# Drivers.net
KiCad netlist of a schematic drawn in Altium Designer
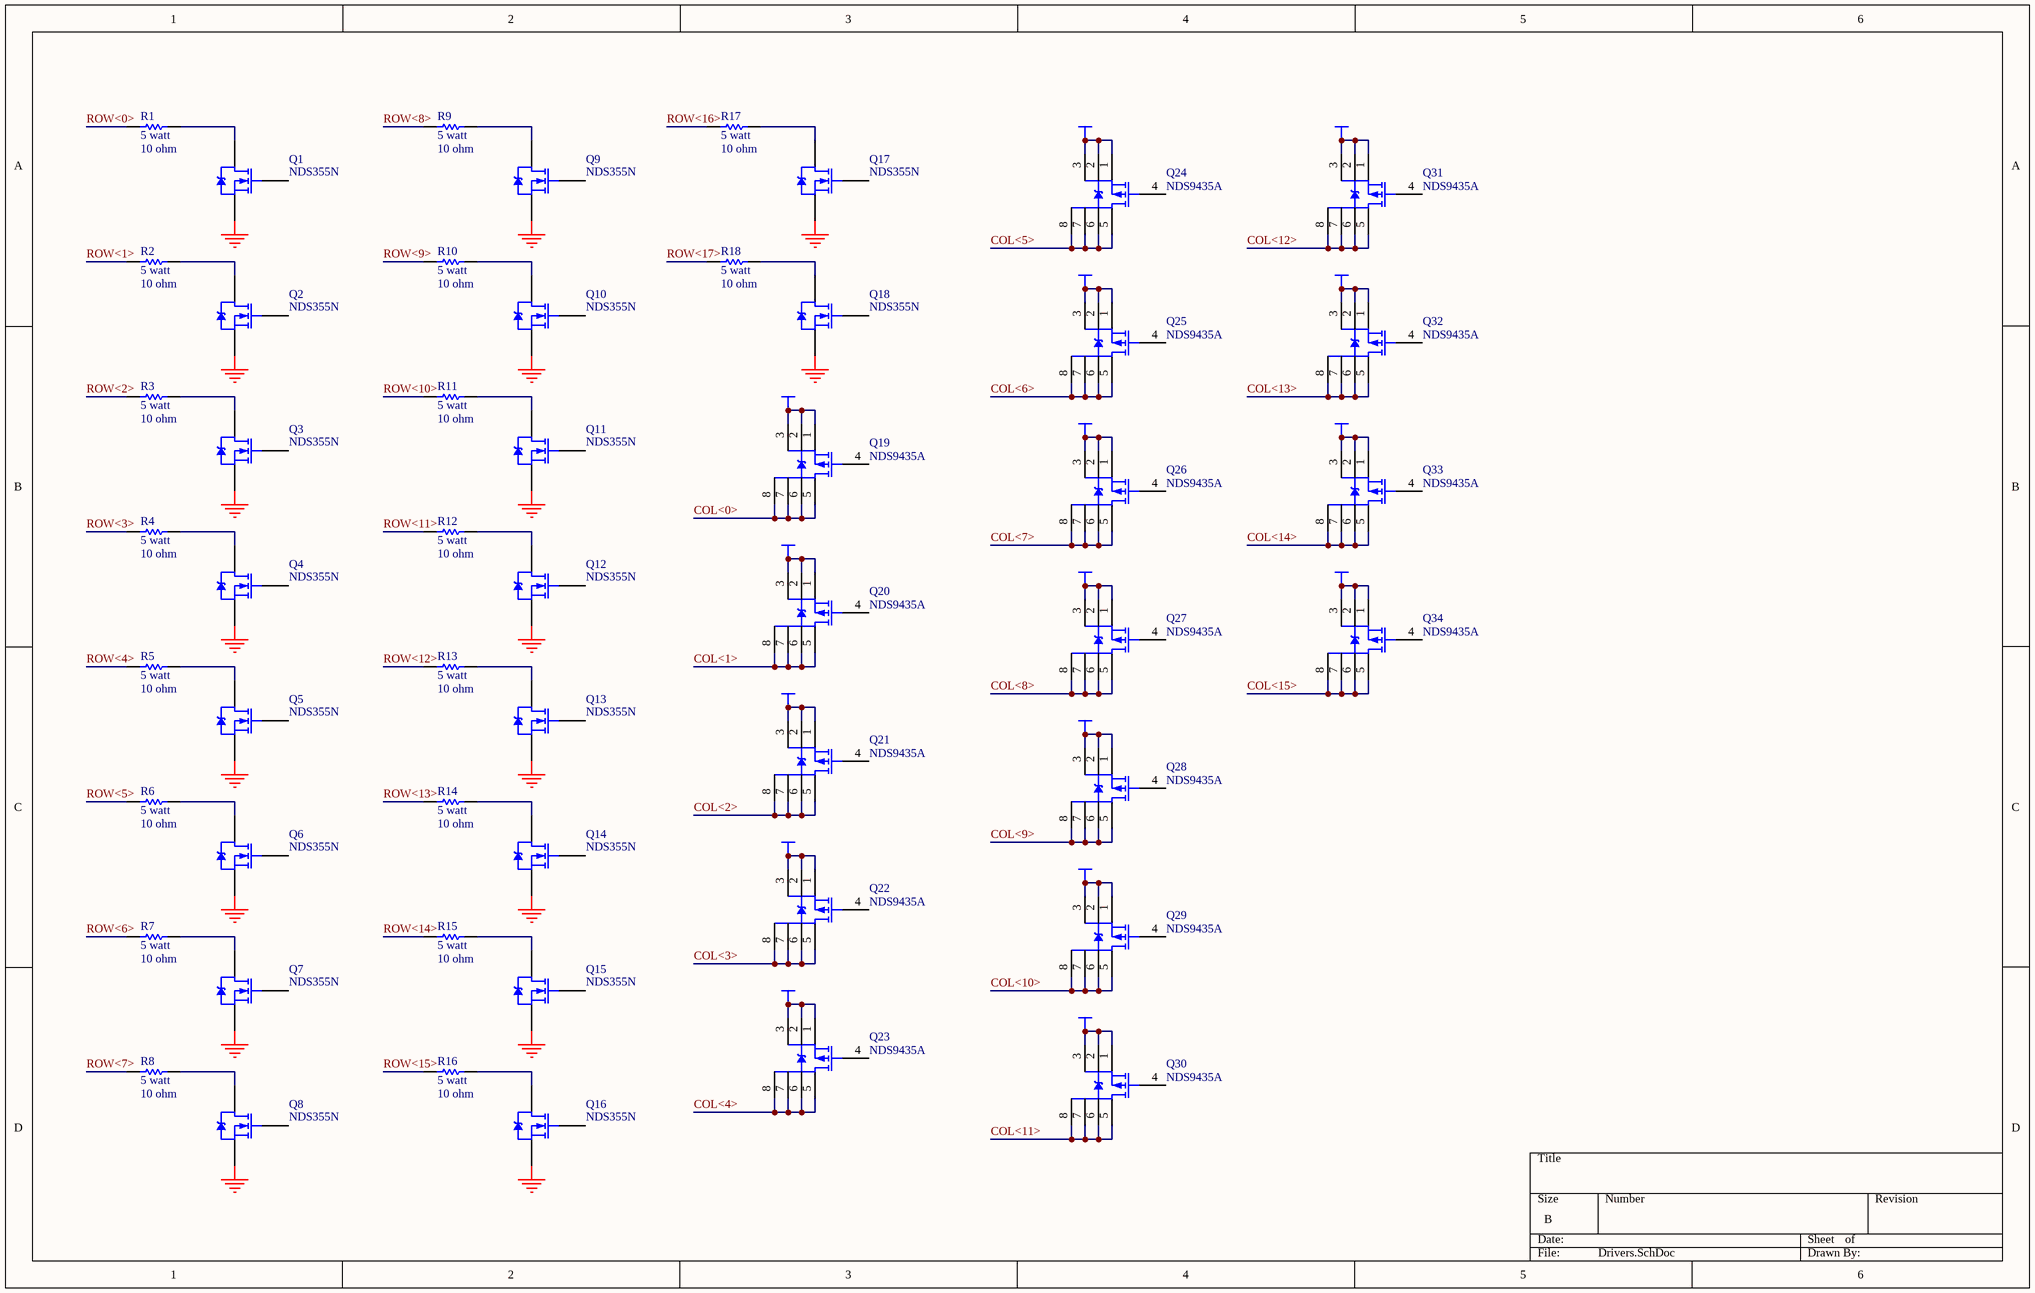
[diagram p0: Drivers.SchDoc]

(export (version "E")
  (design (tool "Eeschema 10.0.6"))
  (components
    (comp (ref "Q1")
      (value "NDS355N")
      (footprint "SO-G3")
      (description "N-Channel Logic Level Enhancement Mode FET")
      (fields (field (name "MANUFACTURER") "Fairchild"))
      (libsource (lib "Schlib1") (part "NDS355N"))
    )
    (comp (ref "Q2")
      (value "NDS355N")
      (footprint "SO-G3")
      (description "N-Channel Logic Level Enhancement Mode FET")
      (fields (field (name "MANUFACTURER") "Fairchild"))
      (libsource (lib "Schlib1") (part "NDS355N"))
    )
    (comp (ref "Q3")
      (value "NDS355N")
      (footprint "SO-G3")
      (description "N-Channel Logic Level Enhancement Mode FET")
      (fields (field (name "MANUFACTURER") "Fairchild"))
      (libsource (lib "Schlib1") (part "NDS355N"))
    )
    (comp (ref "Q4")
      (value "NDS355N")
      (footprint "SO-G3")
      (description "N-Channel Logic Level Enhancement Mode FET")
      (fields (field (name "MANUFACTURER") "Fairchild"))
      (libsource (lib "Schlib1") (part "NDS355N"))
    )
    (comp (ref "Q5")
      (value "NDS355N")
      (footprint "SO-G3")
      (description "N-Channel Logic Level Enhancement Mode FET")
      (fields (field (name "MANUFACTURER") "Fairchild"))
      (libsource (lib "Schlib1") (part "NDS355N"))
    )
    (comp (ref "Q6")
      (value "NDS355N")
      (footprint "SO-G3")
      (description "N-Channel Logic Level Enhancement Mode FET")
      (fields (field (name "MANUFACTURER") "Fairchild"))
      (libsource (lib "Schlib1") (part "NDS355N"))
    )
    (comp (ref "Q7")
      (value "NDS355N")
      (footprint "SO-G3")
      (description "N-Channel Logic Level Enhancement Mode FET")
      (fields (field (name "MANUFACTURER") "Fairchild"))
      (libsource (lib "Schlib1") (part "NDS355N"))
    )
    (comp (ref "Q8")
      (value "NDS355N")
      (footprint "SO-G3")
      (description "N-Channel Logic Level Enhancement Mode FET")
      (fields (field (name "MANUFACTURER") "Fairchild"))
      (libsource (lib "Schlib1") (part "NDS355N"))
    )
    (comp (ref "Q9")
      (value "NDS355N")
      (footprint "SO-G3")
      (description "N-Channel Logic Level Enhancement Mode FET")
      (fields (field (name "MANUFACTURER") "Fairchild"))
      (libsource (lib "Schlib1") (part "NDS355N"))
    )
    (comp (ref "Q10")
      (value "NDS355N")
      (footprint "SO-G3")
      (description "N-Channel Logic Level Enhancement Mode FET")
      (fields (field (name "MANUFACTURER") "Fairchild"))
      (libsource (lib "Schlib1") (part "NDS355N"))
    )
    (comp (ref "Q11")
      (value "NDS355N")
      (footprint "SO-G3")
      (description "N-Channel Logic Level Enhancement Mode FET")
      (fields (field (name "MANUFACTURER") "Fairchild"))
      (libsource (lib "Schlib1") (part "NDS355N"))
    )
    (comp (ref "Q12")
      (value "NDS355N")
      (footprint "SO-G3")
      (description "N-Channel Logic Level Enhancement Mode FET")
      (fields (field (name "MANUFACTURER") "Fairchild"))
      (libsource (lib "Schlib1") (part "NDS355N"))
    )
    (comp (ref "Q13")
      (value "NDS355N")
      (footprint "SO-G3")
      (description "N-Channel Logic Level Enhancement Mode FET")
      (fields (field (name "MANUFACTURER") "Fairchild"))
      (libsource (lib "Schlib1") (part "NDS355N"))
    )
    (comp (ref "Q14")
      (value "NDS355N")
      (footprint "SO-G3")
      (description "N-Channel Logic Level Enhancement Mode FET")
      (fields (field (name "MANUFACTURER") "Fairchild"))
      (libsource (lib "Schlib1") (part "NDS355N"))
    )
    (comp (ref "Q15")
      (value "NDS355N")
      (footprint "SO-G3")
      (description "N-Channel Logic Level Enhancement Mode FET")
      (fields (field (name "MANUFACTURER") "Fairchild"))
      (libsource (lib "Schlib1") (part "NDS355N"))
    )
    (comp (ref "Q16")
      (value "NDS355N")
      (footprint "SO-G3")
      (description "N-Channel Logic Level Enhancement Mode FET")
      (fields (field (name "MANUFACTURER") "Fairchild"))
      (libsource (lib "Schlib1") (part "NDS355N"))
    )
    (comp (ref "Q17")
      (value "NDS355N")
      (footprint "SO-G3")
      (description "N-Channel Logic Level Enhancement Mode FET")
      (fields (field (name "MANUFACTURER") "Fairchild"))
      (libsource (lib "Schlib1") (part "NDS355N"))
    )
    (comp (ref "Q18")
      (value "NDS355N")
      (footprint "SO-G3")
      (description "N-Channel Logic Level Enhancement Mode FET")
      (fields (field (name "MANUFACTURER") "Fairchild"))
      (libsource (lib "Schlib1") (part "NDS355N"))
    )
    (comp (ref "Q19")
      (value "NDS9435A")
      (footprint "SO-G8")
      (description "30V P-Channel PowerTrench MOSFET")
      (fields (field (name "MANUFACTURER") "Fairchild"))
      (libsource (lib "Schlib1") (part "NDS9435A"))
    )
    (comp (ref "Q20")
      (value "NDS9435A")
      (footprint "SO-G8")
      (description "30V P-Channel PowerTrench MOSFET")
      (fields (field (name "MANUFACTURER") "Fairchild"))
      (libsource (lib "Schlib1") (part "NDS9435A"))
    )
    (comp (ref "Q21")
      (value "NDS9435A")
      (footprint "SO-G8")
      (description "30V P-Channel PowerTrench MOSFET")
      (fields (field (name "MANUFACTURER") "Fairchild"))
      (libsource (lib "Schlib1") (part "NDS9435A"))
    )
    (comp (ref "Q22")
      (value "NDS9435A")
      (footprint "SO-G8")
      (description "30V P-Channel PowerTrench MOSFET")
      (fields (field (name "MANUFACTURER") "Fairchild"))
      (libsource (lib "Schlib1") (part "NDS9435A"))
    )
    (comp (ref "Q23")
      (value "NDS9435A")
      (footprint "SO-G8")
      (description "30V P-Channel PowerTrench MOSFET")
      (fields (field (name "MANUFACTURER") "Fairchild"))
      (libsource (lib "Schlib1") (part "NDS9435A"))
    )
    (comp (ref "Q24")
      (value "NDS9435A")
      (footprint "SO-G8")
      (description "30V P-Channel PowerTrench MOSFET")
      (fields (field (name "MANUFACTURER") "Fairchild"))
      (libsource (lib "Schlib1") (part "NDS9435A"))
    )
    (comp (ref "Q25")
      (value "NDS9435A")
      (footprint "SO-G8")
      (description "30V P-Channel PowerTrench MOSFET")
      (fields (field (name "MANUFACTURER") "Fairchild"))
      (libsource (lib "Schlib1") (part "NDS9435A"))
    )
    (comp (ref "Q26")
      (value "NDS9435A")
      (footprint "SO-G8")
      (description "30V P-Channel PowerTrench MOSFET")
      (fields (field (name "MANUFACTURER") "Fairchild"))
      (libsource (lib "Schlib1") (part "NDS9435A"))
    )
    (comp (ref "Q27")
      (value "NDS9435A")
      (footprint "SO-G8")
      (description "30V P-Channel PowerTrench MOSFET")
      (fields (field (name "MANUFACTURER") "Fairchild"))
      (libsource (lib "Schlib1") (part "NDS9435A"))
    )
    (comp (ref "Q28")
      (value "NDS9435A")
      (footprint "SO-G8")
      (description "30V P-Channel PowerTrench MOSFET")
      (fields (field (name "MANUFACTURER") "Fairchild"))
      (libsource (lib "Schlib1") (part "NDS9435A"))
    )
    (comp (ref "Q29")
      (value "NDS9435A")
      (footprint "SO-G8")
      (description "30V P-Channel PowerTrench MOSFET")
      (fields (field (name "MANUFACTURER") "Fairchild"))
      (libsource (lib "Schlib1") (part "NDS9435A"))
    )
    (comp (ref "Q30")
      (value "NDS9435A")
      (footprint "SO-G8")
      (description "30V P-Channel PowerTrench MOSFET")
      (fields (field (name "MANUFACTURER") "Fairchild"))
      (libsource (lib "Schlib1") (part "NDS9435A"))
    )
    (comp (ref "Q31")
      (value "NDS9435A")
      (footprint "SO-G8")
      (description "30V P-Channel PowerTrench MOSFET")
      (fields (field (name "MANUFACTURER") "Fairchild"))
      (libsource (lib "Schlib1") (part "NDS9435A"))
    )
    (comp (ref "Q32")
      (value "NDS9435A")
      (footprint "SO-G8")
      (description "30V P-Channel PowerTrench MOSFET")
      (fields (field (name "MANUFACTURER") "Fairchild"))
      (libsource (lib "Schlib1") (part "NDS9435A"))
    )
    (comp (ref "Q33")
      (value "NDS9435A")
      (footprint "SO-G8")
      (description "30V P-Channel PowerTrench MOSFET")
      (fields (field (name "MANUFACTURER") "Fairchild"))
      (libsource (lib "Schlib1") (part "NDS9435A"))
    )
    (comp (ref "Q34")
      (value "NDS9435A")
      (footprint "SO-G8")
      (description "30V P-Channel PowerTrench MOSFET")
      (fields (field (name "MANUFACTURER") "Fairchild"))
      (libsource (lib "Schlib1") (part "NDS9435A"))
    )
    (comp (ref "R1")
      (value "5 watt")
      (footprint "AXIAL-1.0")
      (description "Resistor")
      (fields
        (field (name "MANUFACTURER") "Generic Components")
        (field (name "ALTIUM_VALUE") "10 ohm")
        (field (name "PUBLISHER") "Altium Limited")
      )
      (libsource (lib "Miscellaneous Devices") (part "Res1"))
    )
    (comp (ref "R2")
      (value "5 watt")
      (footprint "AXIAL-1.0")
      (description "Resistor")
      (fields
        (field (name "MANUFACTURER") "Generic Components")
        (field (name "ALTIUM_VALUE") "10 ohm")
        (field (name "PUBLISHER") "Altium Limited")
      )
      (libsource (lib "Miscellaneous Devices") (part "Res1"))
    )
    (comp (ref "R3")
      (value "5 watt")
      (footprint "AXIAL-1.0")
      (description "Resistor")
      (fields
        (field (name "MANUFACTURER") "Generic Components")
        (field (name "ALTIUM_VALUE") "10 ohm")
        (field (name "PUBLISHER") "Altium Limited")
      )
      (libsource (lib "Miscellaneous Devices") (part "Res1"))
    )
    (comp (ref "R4")
      (value "5 watt")
      (footprint "AXIAL-1.0")
      (description "Resistor")
      (fields
        (field (name "MANUFACTURER") "Generic Components")
        (field (name "ALTIUM_VALUE") "10 ohm")
        (field (name "PUBLISHER") "Altium Limited")
      )
      (libsource (lib "Miscellaneous Devices") (part "Res1"))
    )
    (comp (ref "R5")
      (value "5 watt")
      (footprint "AXIAL-1.0")
      (description "Resistor")
      (fields
        (field (name "MANUFACTURER") "Generic Components")
        (field (name "ALTIUM_VALUE") "10 ohm")
        (field (name "PUBLISHER") "Altium Limited")
      )
      (libsource (lib "Miscellaneous Devices") (part "Res1"))
    )
    (comp (ref "R6")
      (value "5 watt")
      (footprint "AXIAL-1.0")
      (description "Resistor")
      (fields
        (field (name "MANUFACTURER") "Generic Components")
        (field (name "ALTIUM_VALUE") "10 ohm")
        (field (name "PUBLISHER") "Altium Limited")
      )
      (libsource (lib "Miscellaneous Devices") (part "Res1"))
    )
    (comp (ref "R7")
      (value "5 watt")
      (footprint "AXIAL-1.0")
      (description "Resistor")
      (fields
        (field (name "MANUFACTURER") "Generic Components")
        (field (name "ALTIUM_VALUE") "10 ohm")
        (field (name "PUBLISHER") "Altium Limited")
      )
      (libsource (lib "Miscellaneous Devices") (part "Res1"))
    )
    (comp (ref "R8")
      (value "5 watt")
      (footprint "AXIAL-1.0")
      (description "Resistor")
      (fields
        (field (name "MANUFACTURER") "Generic Components")
        (field (name "ALTIUM_VALUE") "10 ohm")
        (field (name "PUBLISHER") "Altium Limited")
      )
      (libsource (lib "Miscellaneous Devices") (part "Res1"))
    )
    (comp (ref "R9")
      (value "5 watt")
      (footprint "AXIAL-1.0")
      (description "Resistor")
      (fields
        (field (name "MANUFACTURER") "Generic Components")
        (field (name "ALTIUM_VALUE") "10 ohm")
        (field (name "PUBLISHER") "Altium Limited")
      )
      (libsource (lib "Miscellaneous Devices") (part "Res1"))
    )
    (comp (ref "R10")
      (value "5 watt")
      (footprint "AXIAL-1.0")
      (description "Resistor")
      (fields
        (field (name "MANUFACTURER") "Generic Components")
        (field (name "ALTIUM_VALUE") "10 ohm")
        (field (name "PUBLISHER") "Altium Limited")
      )
      (libsource (lib "Miscellaneous Devices") (part "Res1"))
    )
    (comp (ref "R11")
      (value "5 watt")
      (footprint "AXIAL-1.0")
      (description "Resistor")
      (fields
        (field (name "MANUFACTURER") "Generic Components")
        (field (name "ALTIUM_VALUE") "10 ohm")
        (field (name "PUBLISHER") "Altium Limited")
      )
      (libsource (lib "Miscellaneous Devices") (part "Res1"))
    )
    (comp (ref "R12")
      (value "5 watt")
      (footprint "AXIAL-1.0")
      (description "Resistor")
      (fields
        (field (name "MANUFACTURER") "Generic Components")
        (field (name "ALTIUM_VALUE") "10 ohm")
        (field (name "PUBLISHER") "Altium Limited")
      )
      (libsource (lib "Miscellaneous Devices") (part "Res1"))
    )
    (comp (ref "R13")
      (value "5 watt")
      (footprint "AXIAL-1.0")
      (description "Resistor")
      (fields
        (field (name "MANUFACTURER") "Generic Components")
        (field (name "ALTIUM_VALUE") "10 ohm")
        (field (name "PUBLISHER") "Altium Limited")
      )
      (libsource (lib "Miscellaneous Devices") (part "Res1"))
    )
    (comp (ref "R14")
      (value "5 watt")
      (footprint "AXIAL-1.0")
      (description "Resistor")
      (fields
        (field (name "MANUFACTURER") "Generic Components")
        (field (name "ALTIUM_VALUE") "10 ohm")
        (field (name "PUBLISHER") "Altium Limited")
      )
      (libsource (lib "Miscellaneous Devices") (part "Res1"))
    )
    (comp (ref "R15")
      (value "5 watt")
      (footprint "AXIAL-1.0")
      (description "Resistor")
      (fields
        (field (name "MANUFACTURER") "Generic Components")
        (field (name "ALTIUM_VALUE") "10 ohm")
        (field (name "PUBLISHER") "Altium Limited")
      )
      (libsource (lib "Miscellaneous Devices") (part "Res1"))
    )
    (comp (ref "R16")
      (value "5 watt")
      (footprint "AXIAL-1.0")
      (description "Resistor")
      (fields
        (field (name "MANUFACTURER") "Generic Components")
        (field (name "ALTIUM_VALUE") "10 ohm")
        (field (name "PUBLISHER") "Altium Limited")
      )
      (libsource (lib "Miscellaneous Devices") (part "Res1"))
    )
    (comp (ref "R17")
      (value "5 watt")
      (footprint "AXIAL-1.0")
      (description "Resistor")
      (fields
        (field (name "MANUFACTURER") "Generic Components")
        (field (name "ALTIUM_VALUE") "10 ohm")
        (field (name "PUBLISHER") "Altium Limited")
      )
      (libsource (lib "Miscellaneous Devices") (part "Res1"))
    )
    (comp (ref "R18")
      (value "5 watt")
      (footprint "AXIAL-1.0")
      (description "Resistor")
      (fields
        (field (name "MANUFACTURER") "Generic Components")
        (field (name "ALTIUM_VALUE") "10 ohm")
        (field (name "PUBLISHER") "Altium Limited")
      )
      (libsource (lib "Miscellaneous Devices") (part "Res1"))
    )
  )
  (nets
    (net (code "1") (name "+5") (class "Default")
      (node (ref "Q19") (pin "1") (pinfunction "S_1") (pintype "passive"))
      (node (ref "Q19") (pin "2") (pinfunction "S_2") (pintype "passive"))
      (node (ref "Q19") (pin "3") (pinfunction "S_3") (pintype "passive"))
      (node (ref "Q20") (pin "1") (pinfunction "S_1") (pintype "passive"))
      (node (ref "Q20") (pin "2") (pinfunction "S_2") (pintype "passive"))
      (node (ref "Q20") (pin "3") (pinfunction "S_3") (pintype "passive"))
      (node (ref "Q21") (pin "1") (pinfunction "S_1") (pintype "passive"))
      (node (ref "Q21") (pin "2") (pinfunction "S_2") (pintype "passive"))
      (node (ref "Q21") (pin "3") (pinfunction "S_3") (pintype "passive"))
      (node (ref "Q22") (pin "1") (pinfunction "S_1") (pintype "passive"))
      (node (ref "Q22") (pin "2") (pinfunction "S_2") (pintype "passive"))
      (node (ref "Q22") (pin "3") (pinfunction "S_3") (pintype "passive"))
      (node (ref "Q23") (pin "1") (pinfunction "S_1") (pintype "passive"))
      (node (ref "Q23") (pin "2") (pinfunction "S_2") (pintype "passive"))
      (node (ref "Q23") (pin "3") (pinfunction "S_3") (pintype "passive"))
      (node (ref "Q24") (pin "1") (pinfunction "S_1") (pintype "passive"))
      (node (ref "Q24") (pin "2") (pinfunction "S_2") (pintype "passive"))
      (node (ref "Q24") (pin "3") (pinfunction "S_3") (pintype "passive"))
      (node (ref "Q25") (pin "1") (pinfunction "S_1") (pintype "passive"))
      (node (ref "Q25") (pin "2") (pinfunction "S_2") (pintype "passive"))
      (node (ref "Q25") (pin "3") (pinfunction "S_3") (pintype "passive"))
      (node (ref "Q26") (pin "1") (pinfunction "S_1") (pintype "passive"))
      (node (ref "Q26") (pin "2") (pinfunction "S_2") (pintype "passive"))
      (node (ref "Q26") (pin "3") (pinfunction "S_3") (pintype "passive"))
      (node (ref "Q27") (pin "1") (pinfunction "S_1") (pintype "passive"))
      (node (ref "Q27") (pin "2") (pinfunction "S_2") (pintype "passive"))
      (node (ref "Q27") (pin "3") (pinfunction "S_3") (pintype "passive"))
      (node (ref "Q28") (pin "1") (pinfunction "S_1") (pintype "passive"))
      (node (ref "Q28") (pin "2") (pinfunction "S_2") (pintype "passive"))
      (node (ref "Q28") (pin "3") (pinfunction "S_3") (pintype "passive"))
      (node (ref "Q29") (pin "1") (pinfunction "S_1") (pintype "passive"))
      (node (ref "Q29") (pin "2") (pinfunction "S_2") (pintype "passive"))
      (node (ref "Q29") (pin "3") (pinfunction "S_3") (pintype "passive"))
      (node (ref "Q30") (pin "1") (pinfunction "S_1") (pintype "passive"))
      (node (ref "Q30") (pin "2") (pinfunction "S_2") (pintype "passive"))
      (node (ref "Q30") (pin "3") (pinfunction "S_3") (pintype "passive"))
      (node (ref "Q31") (pin "1") (pinfunction "S_1") (pintype "passive"))
      (node (ref "Q31") (pin "2") (pinfunction "S_2") (pintype "passive"))
      (node (ref "Q31") (pin "3") (pinfunction "S_3") (pintype "passive"))
      (node (ref "Q32") (pin "1") (pinfunction "S_1") (pintype "passive"))
      (node (ref "Q32") (pin "2") (pinfunction "S_2") (pintype "passive"))
      (node (ref "Q32") (pin "3") (pinfunction "S_3") (pintype "passive"))
      (node (ref "Q33") (pin "1") (pinfunction "S_1") (pintype "passive"))
      (node (ref "Q33") (pin "2") (pinfunction "S_2") (pintype "passive"))
      (node (ref "Q33") (pin "3") (pinfunction "S_3") (pintype "passive"))
      (node (ref "Q34") (pin "1") (pinfunction "S_1") (pintype "passive"))
      (node (ref "Q34") (pin "2") (pinfunction "S_2") (pintype "passive"))
      (node (ref "Q34") (pin "3") (pinfunction "S_3") (pintype "passive"))
    )
    (net (code "2") (name "/COL<0>") (class "Default")
      (node (ref "Q19") (pin "5") (pinfunction "D_5") (pintype "passive"))
      (node (ref "Q19") (pin "6") (pinfunction "D_6") (pintype "passive"))
      (node (ref "Q19") (pin "7") (pinfunction "D_7") (pintype "passive"))
      (node (ref "Q19") (pin "8") (pinfunction "D_8") (pintype "passive"))
    )
    (net (code "3") (name "/COL<1>") (class "Default")
      (node (ref "Q20") (pin "5") (pinfunction "D_5") (pintype "passive"))
      (node (ref "Q20") (pin "6") (pinfunction "D_6") (pintype "passive"))
      (node (ref "Q20") (pin "7") (pinfunction "D_7") (pintype "passive"))
      (node (ref "Q20") (pin "8") (pinfunction "D_8") (pintype "passive"))
    )
    (net (code "4") (name "/COL<2>") (class "Default")
      (node (ref "Q21") (pin "5") (pinfunction "D_5") (pintype "passive"))
      (node (ref "Q21") (pin "6") (pinfunction "D_6") (pintype "passive"))
      (node (ref "Q21") (pin "7") (pinfunction "D_7") (pintype "passive"))
      (node (ref "Q21") (pin "8") (pinfunction "D_8") (pintype "passive"))
    )
    (net (code "5") (name "/COL<3>") (class "Default")
      (node (ref "Q22") (pin "5") (pinfunction "D_5") (pintype "passive"))
      (node (ref "Q22") (pin "6") (pinfunction "D_6") (pintype "passive"))
      (node (ref "Q22") (pin "7") (pinfunction "D_7") (pintype "passive"))
      (node (ref "Q22") (pin "8") (pinfunction "D_8") (pintype "passive"))
    )
    (net (code "6") (name "/COL<4>") (class "Default")
      (node (ref "Q23") (pin "5") (pinfunction "D_5") (pintype "passive"))
      (node (ref "Q23") (pin "6") (pinfunction "D_6") (pintype "passive"))
      (node (ref "Q23") (pin "7") (pinfunction "D_7") (pintype "passive"))
      (node (ref "Q23") (pin "8") (pinfunction "D_8") (pintype "passive"))
    )
    (net (code "7") (name "/COL<5>") (class "Default")
      (node (ref "Q24") (pin "5") (pinfunction "D_5") (pintype "passive"))
      (node (ref "Q24") (pin "6") (pinfunction "D_6") (pintype "passive"))
      (node (ref "Q24") (pin "7") (pinfunction "D_7") (pintype "passive"))
      (node (ref "Q24") (pin "8") (pinfunction "D_8") (pintype "passive"))
    )
    (net (code "8") (name "/COL<6>") (class "Default")
      (node (ref "Q25") (pin "5") (pinfunction "D_5") (pintype "passive"))
      (node (ref "Q25") (pin "6") (pinfunction "D_6") (pintype "passive"))
      (node (ref "Q25") (pin "7") (pinfunction "D_7") (pintype "passive"))
      (node (ref "Q25") (pin "8") (pinfunction "D_8") (pintype "passive"))
    )
    (net (code "9") (name "/COL<7>") (class "Default")
      (node (ref "Q26") (pin "5") (pinfunction "D_5") (pintype "passive"))
      (node (ref "Q26") (pin "6") (pinfunction "D_6") (pintype "passive"))
      (node (ref "Q26") (pin "7") (pinfunction "D_7") (pintype "passive"))
      (node (ref "Q26") (pin "8") (pinfunction "D_8") (pintype "passive"))
    )
    (net (code "10") (name "/COL<8>") (class "Default")
      (node (ref "Q27") (pin "5") (pinfunction "D_5") (pintype "passive"))
      (node (ref "Q27") (pin "6") (pinfunction "D_6") (pintype "passive"))
      (node (ref "Q27") (pin "7") (pinfunction "D_7") (pintype "passive"))
      (node (ref "Q27") (pin "8") (pinfunction "D_8") (pintype "passive"))
    )
    (net (code "11") (name "/COL<9>") (class "Default")
      (node (ref "Q28") (pin "5") (pinfunction "D_5") (pintype "passive"))
      (node (ref "Q28") (pin "6") (pinfunction "D_6") (pintype "passive"))
      (node (ref "Q28") (pin "7") (pinfunction "D_7") (pintype "passive"))
      (node (ref "Q28") (pin "8") (pinfunction "D_8") (pintype "passive"))
    )
    (net (code "12") (name "/COL<10>") (class "Default")
      (node (ref "Q29") (pin "5") (pinfunction "D_5") (pintype "passive"))
      (node (ref "Q29") (pin "6") (pinfunction "D_6") (pintype "passive"))
      (node (ref "Q29") (pin "7") (pinfunction "D_7") (pintype "passive"))
      (node (ref "Q29") (pin "8") (pinfunction "D_8") (pintype "passive"))
    )
    (net (code "13") (name "/COL<11>") (class "Default")
      (node (ref "Q30") (pin "5") (pinfunction "D_5") (pintype "passive"))
      (node (ref "Q30") (pin "6") (pinfunction "D_6") (pintype "passive"))
      (node (ref "Q30") (pin "7") (pinfunction "D_7") (pintype "passive"))
      (node (ref "Q30") (pin "8") (pinfunction "D_8") (pintype "passive"))
    )
    (net (code "14") (name "/COL<12>") (class "Default")
      (node (ref "Q31") (pin "5") (pinfunction "D_5") (pintype "passive"))
      (node (ref "Q31") (pin "6") (pinfunction "D_6") (pintype "passive"))
      (node (ref "Q31") (pin "7") (pinfunction "D_7") (pintype "passive"))
      (node (ref "Q31") (pin "8") (pinfunction "D_8") (pintype "passive"))
    )
    (net (code "15") (name "/COL<13>") (class "Default")
      (node (ref "Q32") (pin "5") (pinfunction "D_5") (pintype "passive"))
      (node (ref "Q32") (pin "6") (pinfunction "D_6") (pintype "passive"))
      (node (ref "Q32") (pin "7") (pinfunction "D_7") (pintype "passive"))
      (node (ref "Q32") (pin "8") (pinfunction "D_8") (pintype "passive"))
    )
    (net (code "16") (name "/COL<14>") (class "Default")
      (node (ref "Q33") (pin "5") (pinfunction "D_5") (pintype "passive"))
      (node (ref "Q33") (pin "6") (pinfunction "D_6") (pintype "passive"))
      (node (ref "Q33") (pin "7") (pinfunction "D_7") (pintype "passive"))
      (node (ref "Q33") (pin "8") (pinfunction "D_8") (pintype "passive"))
    )
    (net (code "17") (name "/COL<15>") (class "Default")
      (node (ref "Q34") (pin "5") (pinfunction "D_5") (pintype "passive"))
      (node (ref "Q34") (pin "6") (pinfunction "D_6") (pintype "passive"))
      (node (ref "Q34") (pin "7") (pinfunction "D_7") (pintype "passive"))
      (node (ref "Q34") (pin "8") (pinfunction "D_8") (pintype "passive"))
    )
    (net (code "18") (name "/ROW<0>") (class "Default")
      (node (ref "R1") (pin "1") (pinfunction "1_1") (pintype "passive"))
    )
    (net (code "19") (name "/ROW<1>") (class "Default")
      (node (ref "R2") (pin "1") (pinfunction "1_1") (pintype "passive"))
    )
    (net (code "20") (name "/ROW<2>") (class "Default")
      (node (ref "R3") (pin "1") (pinfunction "1_1") (pintype "passive"))
    )
    (net (code "21") (name "/ROW<3>") (class "Default")
      (node (ref "R4") (pin "1") (pinfunction "1_1") (pintype "passive"))
    )
    (net (code "22") (name "/ROW<4>") (class "Default")
      (node (ref "R5") (pin "1") (pinfunction "1_1") (pintype "passive"))
    )
    (net (code "23") (name "/ROW<5>") (class "Default")
      (node (ref "R6") (pin "1") (pinfunction "1_1") (pintype "passive"))
    )
    (net (code "24") (name "/ROW<6>") (class "Default")
      (node (ref "R7") (pin "1") (pinfunction "1_1") (pintype "passive"))
    )
    (net (code "25") (name "/ROW<7>") (class "Default")
      (node (ref "R8") (pin "1") (pinfunction "1_1") (pintype "passive"))
    )
    (net (code "26") (name "/ROW<8>") (class "Default")
      (node (ref "R9") (pin "1") (pinfunction "1_1") (pintype "passive"))
    )
    (net (code "27") (name "/ROW<9>") (class "Default")
      (node (ref "R10") (pin "1") (pinfunction "1_1") (pintype "passive"))
    )
    (net (code "28") (name "/ROW<10>") (class "Default")
      (node (ref "R11") (pin "1") (pinfunction "1_1") (pintype "passive"))
    )
    (net (code "29") (name "/ROW<11>") (class "Default")
      (node (ref "R12") (pin "1") (pinfunction "1_1") (pintype "passive"))
    )
    (net (code "30") (name "/ROW<12>") (class "Default")
      (node (ref "R13") (pin "1") (pinfunction "1_1") (pintype "passive"))
    )
    (net (code "31") (name "/ROW<13>") (class "Default")
      (node (ref "R14") (pin "1") (pinfunction "1_1") (pintype "passive"))
    )
    (net (code "32") (name "/ROW<14>") (class "Default")
      (node (ref "R15") (pin "1") (pinfunction "1_1") (pintype "passive"))
    )
    (net (code "33") (name "/ROW<15>") (class "Default")
      (node (ref "R16") (pin "1") (pinfunction "1_1") (pintype "passive"))
    )
    (net (code "34") (name "/ROW<16>") (class "Default")
      (node (ref "R17") (pin "1") (pinfunction "1_1") (pintype "passive"))
    )
    (net (code "35") (name "/ROW<17>") (class "Default")
      (node (ref "R18") (pin "1") (pinfunction "1_1") (pintype "passive"))
    )
    (net (code "36") (name "GND") (class "Default")
      (node (ref "Q1") (pin "2") (pinfunction "S_2") (pintype "passive"))
      (node (ref "Q10") (pin "2") (pinfunction "S_2") (pintype "passive"))
      (node (ref "Q11") (pin "2") (pinfunction "S_2") (pintype "passive"))
      (node (ref "Q12") (pin "2") (pinfunction "S_2") (pintype "passive"))
      (node (ref "Q13") (pin "2") (pinfunction "S_2") (pintype "passive"))
      (node (ref "Q14") (pin "2") (pinfunction "S_2") (pintype "passive"))
      (node (ref "Q15") (pin "2") (pinfunction "S_2") (pintype "passive"))
      (node (ref "Q16") (pin "2") (pinfunction "S_2") (pintype "passive"))
      (node (ref "Q17") (pin "2") (pinfunction "S_2") (pintype "passive"))
      (node (ref "Q18") (pin "2") (pinfunction "S_2") (pintype "passive"))
      (node (ref "Q2") (pin "2") (pinfunction "S_2") (pintype "passive"))
      (node (ref "Q3") (pin "2") (pinfunction "S_2") (pintype "passive"))
      (node (ref "Q4") (pin "2") (pinfunction "S_2") (pintype "passive"))
      (node (ref "Q5") (pin "2") (pinfunction "S_2") (pintype "passive"))
      (node (ref "Q6") (pin "2") (pinfunction "S_2") (pintype "passive"))
      (node (ref "Q7") (pin "2") (pinfunction "S_2") (pintype "passive"))
      (node (ref "Q8") (pin "2") (pinfunction "S_2") (pintype "passive"))
      (node (ref "Q9") (pin "2") (pinfunction "S_2") (pintype "passive"))
    )
    (net (code "37") (name "Net-(Q1-D)") (class "Default")
      (node (ref "Q1") (pin "3") (pinfunction "D_3") (pintype "passive"))
      (node (ref "R1") (pin "2") (pinfunction "2_2") (pintype "passive"))
    )
    (net (code "38") (name "Net-(Q2-D)") (class "Default")
      (node (ref "Q2") (pin "3") (pinfunction "D_3") (pintype "passive"))
      (node (ref "R2") (pin "2") (pinfunction "2_2") (pintype "passive"))
    )
    (net (code "39") (name "Net-(Q3-D)") (class "Default")
      (node (ref "Q3") (pin "3") (pinfunction "D_3") (pintype "passive"))
      (node (ref "R3") (pin "2") (pinfunction "2_2") (pintype "passive"))
    )
    (net (code "40") (name "Net-(Q4-D)") (class "Default")
      (node (ref "Q4") (pin "3") (pinfunction "D_3") (pintype "passive"))
      (node (ref "R4") (pin "2") (pinfunction "2_2") (pintype "passive"))
    )
    (net (code "41") (name "Net-(Q5-D)") (class "Default")
      (node (ref "Q5") (pin "3") (pinfunction "D_3") (pintype "passive"))
      (node (ref "R5") (pin "2") (pinfunction "2_2") (pintype "passive"))
    )
    (net (code "42") (name "Net-(Q6-D)") (class "Default")
      (node (ref "Q6") (pin "3") (pinfunction "D_3") (pintype "passive"))
      (node (ref "R6") (pin "2") (pinfunction "2_2") (pintype "passive"))
    )
    (net (code "43") (name "Net-(Q7-D)") (class "Default")
      (node (ref "Q7") (pin "3") (pinfunction "D_3") (pintype "passive"))
      (node (ref "R7") (pin "2") (pinfunction "2_2") (pintype "passive"))
    )
    (net (code "44") (name "Net-(Q8-D)") (class "Default")
      (node (ref "Q8") (pin "3") (pinfunction "D_3") (pintype "passive"))
      (node (ref "R8") (pin "2") (pinfunction "2_2") (pintype "passive"))
    )
    (net (code "45") (name "Net-(Q9-D)") (class "Default")
      (node (ref "Q9") (pin "3") (pinfunction "D_3") (pintype "passive"))
      (node (ref "R9") (pin "2") (pinfunction "2_2") (pintype "passive"))
    )
    (net (code "46") (name "Net-(Q10-D)") (class "Default")
      (node (ref "Q10") (pin "3") (pinfunction "D_3") (pintype "passive"))
      (node (ref "R10") (pin "2") (pinfunction "2_2") (pintype "passive"))
    )
    (net (code "47") (name "Net-(Q11-D)") (class "Default")
      (node (ref "Q11") (pin "3") (pinfunction "D_3") (pintype "passive"))
      (node (ref "R11") (pin "2") (pinfunction "2_2") (pintype "passive"))
    )
    (net (code "48") (name "Net-(Q12-D)") (class "Default")
      (node (ref "Q12") (pin "3") (pinfunction "D_3") (pintype "passive"))
      (node (ref "R12") (pin "2") (pinfunction "2_2") (pintype "passive"))
    )
    (net (code "49") (name "Net-(Q13-D)") (class "Default")
      (node (ref "Q13") (pin "3") (pinfunction "D_3") (pintype "passive"))
      (node (ref "R13") (pin "2") (pinfunction "2_2") (pintype "passive"))
    )
    (net (code "50") (name "Net-(Q14-D)") (class "Default")
      (node (ref "Q14") (pin "3") (pinfunction "D_3") (pintype "passive"))
      (node (ref "R14") (pin "2") (pinfunction "2_2") (pintype "passive"))
    )
    (net (code "51") (name "Net-(Q15-D)") (class "Default")
      (node (ref "Q15") (pin "3") (pinfunction "D_3") (pintype "passive"))
      (node (ref "R15") (pin "2") (pinfunction "2_2") (pintype "passive"))
    )
    (net (code "52") (name "Net-(Q16-D)") (class "Default")
      (node (ref "Q16") (pin "3") (pinfunction "D_3") (pintype "passive"))
      (node (ref "R16") (pin "2") (pinfunction "2_2") (pintype "passive"))
    )
    (net (code "53") (name "Net-(Q17-D)") (class "Default")
      (node (ref "Q17") (pin "3") (pinfunction "D_3") (pintype "passive"))
      (node (ref "R17") (pin "2") (pinfunction "2_2") (pintype "passive"))
    )
    (net (code "54") (name "Net-(Q18-D)") (class "Default")
      (node (ref "Q18") (pin "3") (pinfunction "D_3") (pintype "passive"))
      (node (ref "R18") (pin "2") (pinfunction "2_2") (pintype "passive"))
    )
    (net (code "55") (name "unconnected-(Q1-G-Pad1)") (class "Default")
      (node (ref "Q1") (pin "1") (pinfunction "G_1") (pintype "passive"))
    )
    (net (code "56") (name "unconnected-(Q2-G-Pad1)") (class "Default")
      (node (ref "Q2") (pin "1") (pinfunction "G_1") (pintype "passive"))
    )
    (net (code "57") (name "unconnected-(Q3-G-Pad1)") (class "Default")
      (node (ref "Q3") (pin "1") (pinfunction "G_1") (pintype "passive"))
    )
    (net (code "58") (name "unconnected-(Q4-G-Pad1)") (class "Default")
      (node (ref "Q4") (pin "1") (pinfunction "G_1") (pintype "passive"))
    )
    (net (code "59") (name "unconnected-(Q5-G-Pad1)") (class "Default")
      (node (ref "Q5") (pin "1") (pinfunction "G_1") (pintype "passive"))
    )
    (net (code "60") (name "unconnected-(Q6-G-Pad1)") (class "Default")
      (node (ref "Q6") (pin "1") (pinfunction "G_1") (pintype "passive"))
    )
    (net (code "61") (name "unconnected-(Q7-G-Pad1)") (class "Default")
      (node (ref "Q7") (pin "1") (pinfunction "G_1") (pintype "passive"))
    )
    (net (code "62") (name "unconnected-(Q8-G-Pad1)") (class "Default")
      (node (ref "Q8") (pin "1") (pinfunction "G_1") (pintype "passive"))
    )
    (net (code "63") (name "unconnected-(Q9-G-Pad1)") (class "Default")
      (node (ref "Q9") (pin "1") (pinfunction "G_1") (pintype "passive"))
    )
    (net (code "64") (name "unconnected-(Q10-G-Pad1)") (class "Default")
      (node (ref "Q10") (pin "1") (pinfunction "G_1") (pintype "passive"))
    )
    (net (code "65") (name "unconnected-(Q11-G-Pad1)") (class "Default")
      (node (ref "Q11") (pin "1") (pinfunction "G_1") (pintype "passive"))
    )
    (net (code "66") (name "unconnected-(Q12-G-Pad1)") (class "Default")
      (node (ref "Q12") (pin "1") (pinfunction "G_1") (pintype "passive"))
    )
    (net (code "67") (name "unconnected-(Q13-G-Pad1)") (class "Default")
      (node (ref "Q13") (pin "1") (pinfunction "G_1") (pintype "passive"))
    )
    (net (code "68") (name "unconnected-(Q14-G-Pad1)") (class "Default")
      (node (ref "Q14") (pin "1") (pinfunction "G_1") (pintype "passive"))
    )
    (net (code "69") (name "unconnected-(Q15-G-Pad1)") (class "Default")
      (node (ref "Q15") (pin "1") (pinfunction "G_1") (pintype "passive"))
    )
    (net (code "70") (name "unconnected-(Q16-G-Pad1)") (class "Default")
      (node (ref "Q16") (pin "1") (pinfunction "G_1") (pintype "passive"))
    )
    (net (code "71") (name "unconnected-(Q17-G-Pad1)") (class "Default")
      (node (ref "Q17") (pin "1") (pinfunction "G_1") (pintype "passive"))
    )
    (net (code "72") (name "unconnected-(Q18-G-Pad1)") (class "Default")
      (node (ref "Q18") (pin "1") (pinfunction "G_1") (pintype "passive"))
    )
    (net (code "73") (name "unconnected-(Q19-G-Pad4)") (class "Default")
      (node (ref "Q19") (pin "4") (pinfunction "G_4") (pintype "passive"))
    )
    (net (code "74") (name "unconnected-(Q20-G-Pad4)") (class "Default")
      (node (ref "Q20") (pin "4") (pinfunction "G_4") (pintype "passive"))
    )
    (net (code "75") (name "unconnected-(Q21-G-Pad4)") (class "Default")
      (node (ref "Q21") (pin "4") (pinfunction "G_4") (pintype "passive"))
    )
    (net (code "76") (name "unconnected-(Q22-G-Pad4)") (class "Default")
      (node (ref "Q22") (pin "4") (pinfunction "G_4") (pintype "passive"))
    )
    (net (code "77") (name "unconnected-(Q23-G-Pad4)") (class "Default")
      (node (ref "Q23") (pin "4") (pinfunction "G_4") (pintype "passive"))
    )
    (net (code "78") (name "unconnected-(Q24-G-Pad4)") (class "Default")
      (node (ref "Q24") (pin "4") (pinfunction "G_4") (pintype "passive"))
    )
    (net (code "79") (name "unconnected-(Q25-G-Pad4)") (class "Default")
      (node (ref "Q25") (pin "4") (pinfunction "G_4") (pintype "passive"))
    )
    (net (code "80") (name "unconnected-(Q26-G-Pad4)") (class "Default")
      (node (ref "Q26") (pin "4") (pinfunction "G_4") (pintype "passive"))
    )
    (net (code "81") (name "unconnected-(Q27-G-Pad4)") (class "Default")
      (node (ref "Q27") (pin "4") (pinfunction "G_4") (pintype "passive"))
    )
    (net (code "82") (name "unconnected-(Q28-G-Pad4)") (class "Default")
      (node (ref "Q28") (pin "4") (pinfunction "G_4") (pintype "passive"))
    )
    (net (code "83") (name "unconnected-(Q29-G-Pad4)") (class "Default")
      (node (ref "Q29") (pin "4") (pinfunction "G_4") (pintype "passive"))
    )
    (net (code "84") (name "unconnected-(Q30-G-Pad4)") (class "Default")
      (node (ref "Q30") (pin "4") (pinfunction "G_4") (pintype "passive"))
    )
    (net (code "85") (name "unconnected-(Q31-G-Pad4)") (class "Default")
      (node (ref "Q31") (pin "4") (pinfunction "G_4") (pintype "passive"))
    )
    (net (code "86") (name "unconnected-(Q32-G-Pad4)") (class "Default")
      (node (ref "Q32") (pin "4") (pinfunction "G_4") (pintype "passive"))
    )
    (net (code "87") (name "unconnected-(Q33-G-Pad4)") (class "Default")
      (node (ref "Q33") (pin "4") (pinfunction "G_4") (pintype "passive"))
    )
    (net (code "88") (name "unconnected-(Q34-G-Pad4)") (class "Default")
      (node (ref "Q34") (pin "4") (pinfunction "G_4") (pintype "passive"))
    )
  )
)
